# SDCardButtonLed.net
KiCad netlist of a schematic drawn in Altium Designer
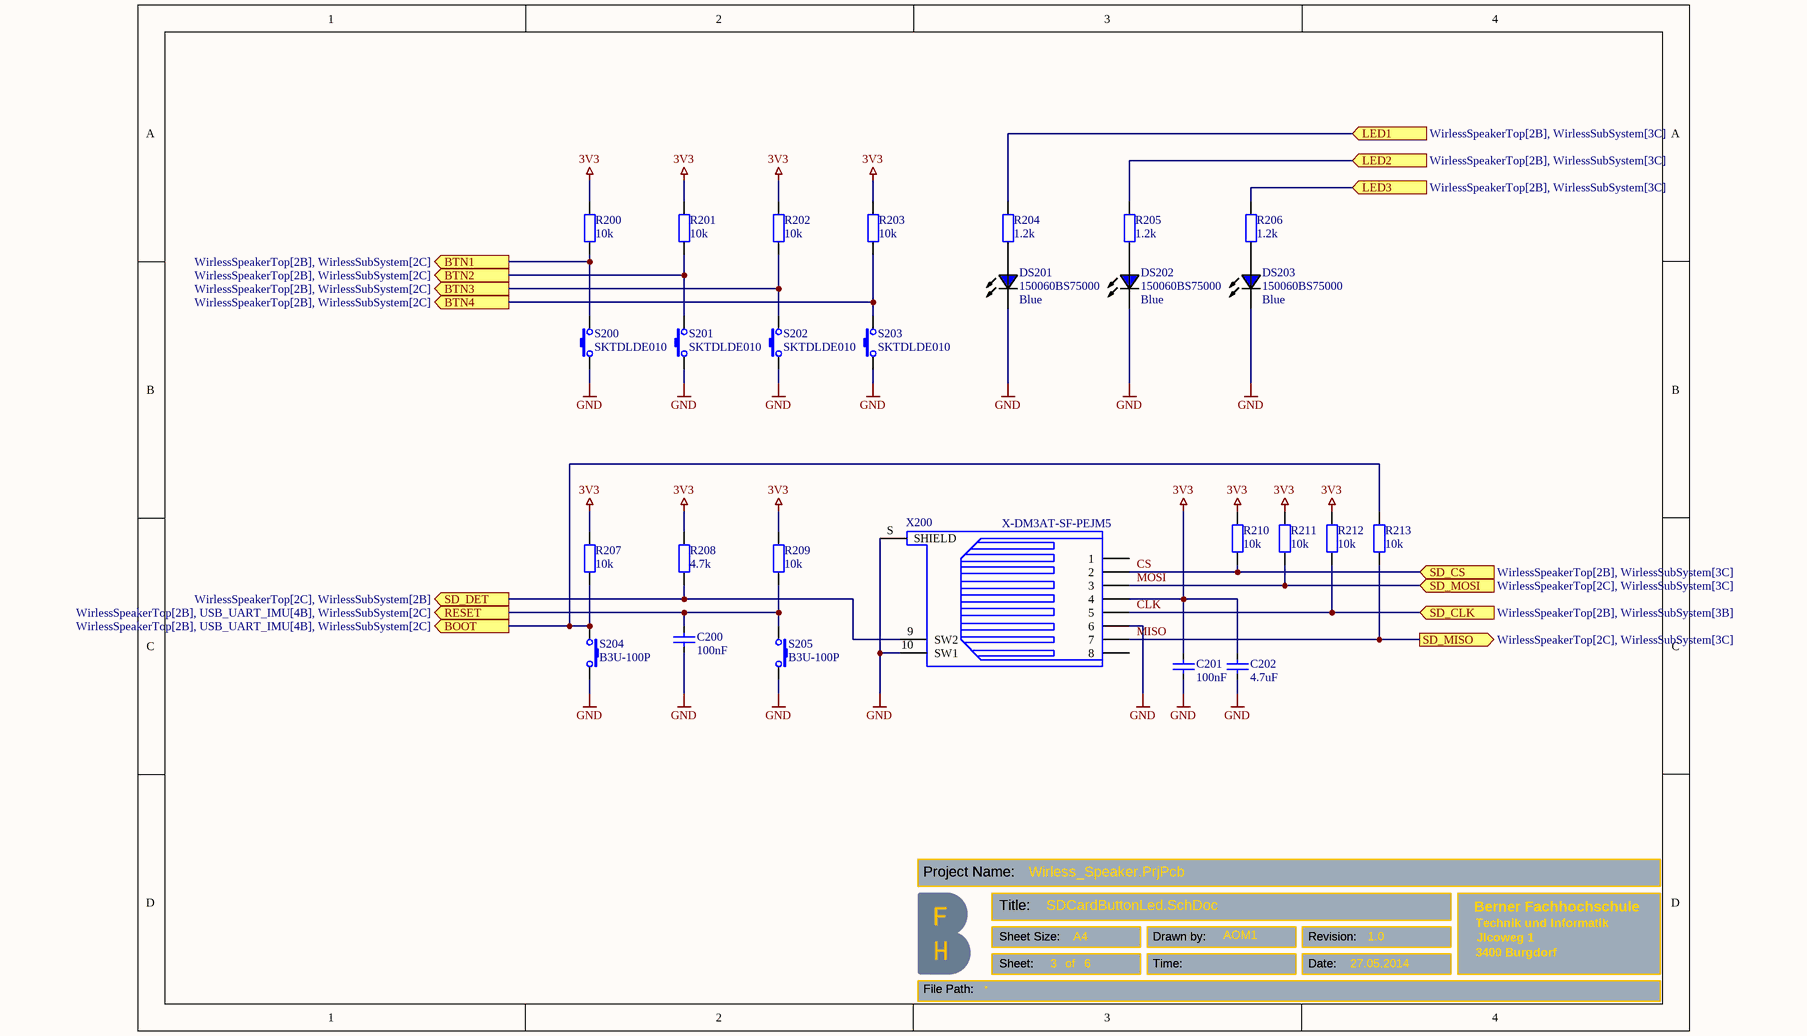
[diagram p0: SDCardButtonLed.SchDoc]

(export (version "E")
  (design (tool "Eeschema 10.0.6"))
  (components
    (comp (ref "C200")
      (value "100nF")
      (footprint "C-0603")
      (description "Multilayer Ceramic Capacitors MLCC")
      (fields (field (name "MANUFACTURER") "Murata Electronics") (field (name "MFR. PART NO.") "GRM18..."))
      (libsource (lib "WirelessAudioSpeaker") (part "C-SMD-0603"))
    )
    (comp (ref "C201")
      (value "100nF")
      (footprint "C-0603")
      (description "Multilayer Ceramic Capacitors MLCC")
      (fields (field (name "MANUFACTURER") "Murata Electronics") (field (name "MFR. PART NO.") "GRM18..."))
      (libsource (lib "WirelessAudioSpeaker") (part "C-SMD-0603"))
    )
    (comp (ref "C202")
      (value "4.7uF")
      (footprint "C-0603")
      (description "Multilayer Ceramic Capacitors MLCC")
      (fields (field (name "MANUFACTURER") "Murata Electronics") (field (name "MFR. PART NO.") "GRM18..."))
      (libsource (lib "WirelessAudioSpeaker") (part "C-SMD-0603"))
    )
    (comp (ref "DS201")
      (value "150060BS75000")
      (footprint "LED-0603-BLUE")
      (description "Standard LEDs - SMD 0603 Blue")
      (fields (field (name "MANUFACTURER") "Wurth Elektronik") (field (name "ALTIUM_VALUE") "Blue"))
      (libsource (lib "WirelessAudioSpeaker") (part "DS-LED-BLUE"))
    )
    (comp (ref "DS202")
      (value "150060BS75000")
      (footprint "LED-0603-BLUE")
      (description "Standard LEDs - SMD 0603 Blue")
      (fields (field (name "MANUFACTURER") "Wurth Elektronik") (field (name "ALTIUM_VALUE") "Blue"))
      (libsource (lib "WirelessAudioSpeaker") (part "DS-LED-BLUE"))
    )
    (comp (ref "DS203")
      (value "150060BS75000")
      (footprint "LED-0603-BLUE")
      (description "Standard LEDs - SMD 0603 Blue")
      (fields (field (name "MANUFACTURER") "Wurth Elektronik") (field (name "ALTIUM_VALUE") "Blue"))
      (libsource (lib "WirelessAudioSpeaker") (part "DS-LED-BLUE"))
    )
    (comp (ref "R200")
      (value "10k")
      (footprint "R-0603")
      (description "Thin Film Resistors - SMD  0.1W  1%")
      (fields (field (name "MFR. PART NO.") "MCU08050C*") (field (name "MANUFACTURER") "Vishay / Beyschlag"))
      (libsource (lib "WirelessAudioSpeaker") (part "R-SMD-0603"))
    )
    (comp (ref "R201")
      (value "10k")
      (footprint "R-0603")
      (description "Thin Film Resistors - SMD  0.1W  1%")
      (fields (field (name "MFR. PART NO.") "MCU08050C*") (field (name "MANUFACTURER") "Vishay / Beyschlag"))
      (libsource (lib "WirelessAudioSpeaker") (part "R-SMD-0603"))
    )
    (comp (ref "R202")
      (value "10k")
      (footprint "R-0603")
      (description "Thin Film Resistors - SMD  0.1W  1%")
      (fields (field (name "MFR. PART NO.") "MCU08050C*") (field (name "MANUFACTURER") "Vishay / Beyschlag"))
      (libsource (lib "WirelessAudioSpeaker") (part "R-SMD-0603"))
    )
    (comp (ref "R203")
      (value "10k")
      (footprint "R-0603")
      (description "Thin Film Resistors - SMD  0.1W  1%")
      (fields (field (name "MFR. PART NO.") "MCU08050C*") (field (name "MANUFACTURER") "Vishay / Beyschlag"))
      (libsource (lib "WirelessAudioSpeaker") (part "R-SMD-0603"))
    )
    (comp (ref "R204")
      (value "1.2k")
      (footprint "R-0603")
      (description "Thin Film Resistors - SMD  0.1W  1%")
      (fields (field (name "MFR. PART NO.") "MCU08050C*") (field (name "MANUFACTURER") "Vishay / Beyschlag"))
      (libsource (lib "WirelessAudioSpeaker") (part "R-SMD-0603"))
    )
    (comp (ref "R205")
      (value "1.2k")
      (footprint "R-0603")
      (description "Thin Film Resistors - SMD  0.1W  1%")
      (fields (field (name "MFR. PART NO.") "MCU08050C*") (field (name "MANUFACTURER") "Vishay / Beyschlag"))
      (libsource (lib "WirelessAudioSpeaker") (part "R-SMD-0603"))
    )
    (comp (ref "R206")
      (value "1.2k")
      (footprint "R-0603")
      (description "Thin Film Resistors - SMD  0.1W  1%")
      (fields (field (name "MFR. PART NO.") "MCU08050C*") (field (name "MANUFACTURER") "Vishay / Beyschlag"))
      (libsource (lib "WirelessAudioSpeaker") (part "R-SMD-0603"))
    )
    (comp (ref "R207")
      (value "10k")
      (footprint "R-0603")
      (description "Thin Film Resistors - SMD  0.1W  1%")
      (fields (field (name "MFR. PART NO.") "MCU08050C*") (field (name "MANUFACTURER") "Vishay / Beyschlag"))
      (libsource (lib "WirelessAudioSpeaker") (part "R-SMD-0603"))
    )
    (comp (ref "R208")
      (value "4.7k")
      (footprint "R-0603")
      (description "Thin Film Resistors - SMD  0.1W  1%")
      (fields (field (name "MFR. PART NO.") "MCU08050C*") (field (name "MANUFACTURER") "Vishay / Beyschlag"))
      (libsource (lib "WirelessAudioSpeaker") (part "R-SMD-0603"))
    )
    (comp (ref "R209")
      (value "10k")
      (footprint "R-0603")
      (description "Thin Film Resistors - SMD  0.1W  1%")
      (fields (field (name "MFR. PART NO.") "MCU08050C*") (field (name "MANUFACTURER") "Vishay / Beyschlag"))
      (libsource (lib "WirelessAudioSpeaker") (part "R-SMD-0603"))
    )
    (comp (ref "R210")
      (value "10k")
      (footprint "R-0603")
      (description "Thin Film Resistors - SMD  0.1W  1%")
      (fields (field (name "MFR. PART NO.") "MCU08050C*") (field (name "MANUFACTURER") "Vishay / Beyschlag"))
      (libsource (lib "WirelessAudioSpeaker") (part "R-SMD-0603"))
    )
    (comp (ref "R211")
      (value "10k")
      (footprint "R-0603")
      (description "Thin Film Resistors - SMD  0.1W  1%")
      (fields (field (name "MFR. PART NO.") "MCU08050C*") (field (name "MANUFACTURER") "Vishay / Beyschlag"))
      (libsource (lib "WirelessAudioSpeaker") (part "R-SMD-0603"))
    )
    (comp (ref "R212")
      (value "10k")
      (footprint "R-0603")
      (description "Thin Film Resistors - SMD  0.1W  1%")
      (fields (field (name "MFR. PART NO.") "MCU08050C*") (field (name "MANUFACTURER") "Vishay / Beyschlag"))
      (libsource (lib "WirelessAudioSpeaker") (part "R-SMD-0603"))
    )
    (comp (ref "R213")
      (value "10k")
      (footprint "R-0603")
      (description "Thin Film Resistors - SMD  0.1W  1%")
      (fields (field (name "MFR. PART NO.") "MCU08050C*") (field (name "MANUFACTURER") "Vishay / Beyschlag"))
      (libsource (lib "WirelessAudioSpeaker") (part "R-SMD-0603"))
    )
    (comp (ref "S200")
      (value "SKTDLDE010")
      (footprint "S-SKTDLDE010")
      (description "Tactile Switches 6x6 Flat 4.3mm Btn Force 100g w/o Grd")
      (fields (field (name "MANUFACTURER") "ALPS"))
      (libsource (lib "WirelessAudioSpeaker") (part "S-Tactile-Switch"))
    )
    (comp (ref "S201")
      (value "SKTDLDE010")
      (footprint "S-SKTDLDE010")
      (description "Tactile Switches 6x6 Flat 4.3mm Btn Force 100g w/o Grd")
      (fields (field (name "MANUFACTURER") "ALPS"))
      (libsource (lib "WirelessAudioSpeaker") (part "S-Tactile-Switch"))
    )
    (comp (ref "S202")
      (value "SKTDLDE010")
      (footprint "S-SKTDLDE010")
      (description "Tactile Switches 6x6 Flat 4.3mm Btn Force 100g w/o Grd")
      (fields (field (name "MANUFACTURER") "ALPS"))
      (libsource (lib "WirelessAudioSpeaker") (part "S-Tactile-Switch"))
    )
    (comp (ref "S203")
      (value "SKTDLDE010")
      (footprint "S-SKTDLDE010")
      (description "Tactile Switches 6x6 Flat 4.3mm Btn Force 100g w/o Grd")
      (fields (field (name "MANUFACTURER") "ALPS"))
      (libsource (lib "WirelessAudioSpeaker") (part "S-Tactile-Switch"))
    )
    (comp (ref "S204")
      (value "B3U-100P")
      (footprint "S-B3U-100X")
      (description "Tactile Switches Top Actuated w/o boss w/o ground")
      (fields
        (field (name "MANUFACTURER") "OMRON ELECTRONIC COMPONENTS")
        (field (name "MFR. PART NO.") "B3U-1000P")
      )
      (libsource (lib "WirelessAudioSpeaker") (part "S-B3U-100P"))
    )
    (comp (ref "S205")
      (value "B3U-100P")
      (footprint "S-B3U-100X")
      (description "Tactile Switches Top Actuated w/o boss w/o ground")
      (fields
        (field (name "MANUFACTURER") "OMRON ELECTRONIC COMPONENTS")
        (field (name "MFR. PART NO.") "B3U-1000P")
      )
      (libsource (lib "WirelessAudioSpeaker") (part "S-B3U-100P"))
    )
    (comp (ref "X200")
      (value "X-DM3AT-SF-PEJM5")
      (footprint "X-DM3AT-SF-PEJM5")
      (description "SMTMicro SD 8 Pin PCB")
      (fields
        (field (name "MANUFACTURER") "Hirose Electric Co Ltd")
        (field (name "MFR. PART NO.") "DM3AT-SF-PEJM5")
      )
      (libsource (lib "WirelessAudioSpeaker") (part "X-DM3AT-SF-PEJM5"))
    )
  )
  (nets
    (net (code "1") (name "/BOOT") (class "Default")
      (node (ref "R207") (pin "1") (pinfunction "1_1") (pintype "passive"))
      (node (ref "R213") (pin "2") (pinfunction "2_2") (pintype "passive"))
      (node (ref "S204") (pin "1") (pinfunction "1_1") (pintype "passive"))
    )
    (net (code "2") (name "/BTN1") (class "Default")
      (node (ref "R200") (pin "1") (pinfunction "1_1") (pintype "passive"))
      (node (ref "S200") (pin "2") (pinfunction "2_2") (pintype "passive"))
    )
    (net (code "3") (name "/BTN2") (class "Default")
      (node (ref "R201") (pin "1") (pinfunction "1_1") (pintype "passive"))
      (node (ref "S201") (pin "2") (pinfunction "2_2") (pintype "passive"))
    )
    (net (code "4") (name "/BTN3") (class "Default")
      (node (ref "R202") (pin "1") (pinfunction "1_1") (pintype "passive"))
      (node (ref "S202") (pin "2") (pinfunction "2_2") (pintype "passive"))
    )
    (net (code "5") (name "/BTN4") (class "Default")
      (node (ref "R203") (pin "1") (pinfunction "1_1") (pintype "passive"))
      (node (ref "S203") (pin "2") (pinfunction "2_2") (pintype "passive"))
    )
    (net (code "6") (name "/CLK") (class "Default")
      (node (ref "R212") (pin "1") (pinfunction "1_1") (pintype "passive"))
      (node (ref "X200") (pin "5") (pinfunction "5_5") (pintype "passive"))
    )
    (net (code "7") (name "/CS") (class "Default")
      (node (ref "R210") (pin "1") (pinfunction "1_1") (pintype "passive"))
      (node (ref "X200") (pin "2") (pinfunction "2_2") (pintype "passive"))
    )
    (net (code "8") (name "/LED1") (class "Default")
      (node (ref "R204") (pin "2") (pinfunction "2_2") (pintype "passive"))
    )
    (net (code "9") (name "/LED2") (class "Default")
      (node (ref "R205") (pin "2") (pinfunction "2_2") (pintype "passive"))
    )
    (net (code "10") (name "/LED3") (class "Default")
      (node (ref "R206") (pin "2") (pinfunction "2_2") (pintype "passive"))
    )
    (net (code "11") (name "/MISO") (class "Default")
      (node (ref "R213") (pin "1") (pinfunction "1_1") (pintype "passive"))
      (node (ref "X200") (pin "7") (pinfunction "7_7") (pintype "passive"))
    )
    (net (code "12") (name "/MOSI") (class "Default")
      (node (ref "R211") (pin "1") (pinfunction "1_1") (pintype "passive"))
      (node (ref "X200") (pin "3") (pinfunction "3_3") (pintype "passive"))
    )
    (net (code "13") (name "/RESET") (class "Default")
      (node (ref "C200") (pin "2") (pinfunction "2_2") (pintype "passive"))
      (node (ref "R209") (pin "1") (pinfunction "1_1") (pintype "passive"))
      (node (ref "S205") (pin "1") (pinfunction "1_1") (pintype "passive"))
    )
    (net (code "14") (name "/SD_DET") (class "Default")
      (node (ref "R208") (pin "1") (pinfunction "1_1") (pintype "passive"))
      (node (ref "X200") (pin "9") (pinfunction "SW2_9") (pintype "passive"))
    )
    (net (code "15") (name "3V3") (class "Default")
      (node (ref "C201") (pin "2") (pinfunction "2_2") (pintype "passive"))
      (node (ref "C202") (pin "2") (pinfunction "2_2") (pintype "passive"))
      (node (ref "R200") (pin "2") (pinfunction "2_2") (pintype "passive"))
      (node (ref "R201") (pin "2") (pinfunction "2_2") (pintype "passive"))
      (node (ref "R202") (pin "2") (pinfunction "2_2") (pintype "passive"))
      (node (ref "R203") (pin "2") (pinfunction "2_2") (pintype "passive"))
      (node (ref "R207") (pin "2") (pinfunction "2_2") (pintype "passive"))
      (node (ref "R208") (pin "2") (pinfunction "2_2") (pintype "passive"))
      (node (ref "R209") (pin "2") (pinfunction "2_2") (pintype "passive"))
      (node (ref "R210") (pin "2") (pinfunction "2_2") (pintype "passive"))
      (node (ref "R211") (pin "2") (pinfunction "2_2") (pintype "passive"))
      (node (ref "R212") (pin "2") (pinfunction "2_2") (pintype "passive"))
      (node (ref "X200") (pin "4") (pinfunction "4_4") (pintype "passive"))
    )
    (net (code "16") (name "GND") (class "Default")
      (node (ref "C200") (pin "1") (pinfunction "1_1") (pintype "passive"))
      (node (ref "C201") (pin "1") (pinfunction "1_1") (pintype "passive"))
      (node (ref "C202") (pin "1") (pinfunction "1_1") (pintype "passive"))
      (node (ref "DS201") (pin "K") (pinfunction "K_K") (pintype "passive"))
      (node (ref "DS202") (pin "K") (pinfunction "K_K") (pintype "passive"))
      (node (ref "DS203") (pin "K") (pinfunction "K_K") (pintype "passive"))
      (node (ref "S200") (pin "1") (pinfunction "1_1") (pintype "passive"))
      (node (ref "S201") (pin "1") (pinfunction "1_1") (pintype "passive"))
      (node (ref "S202") (pin "1") (pinfunction "1_1") (pintype "passive"))
      (node (ref "S203") (pin "1") (pinfunction "1_1") (pintype "passive"))
      (node (ref "S204") (pin "2") (pinfunction "2_2") (pintype "passive"))
      (node (ref "S205") (pin "2") (pinfunction "2_2") (pintype "passive"))
      (node (ref "X200") (pin "10") (pinfunction "SW1_10") (pintype "passive"))
      (node (ref "X200") (pin "6") (pinfunction "6_6") (pintype "passive"))
      (node (ref "X200") (pin "S") (pinfunction "SHIELD_S") (pintype "passive"))
    )
    (net (code "17") (name "Net-(DS201-PadA)") (class "Default")
      (node (ref "DS201") (pin "A") (pinfunction "A_A") (pintype "passive"))
      (node (ref "R204") (pin "1") (pinfunction "1_1") (pintype "passive"))
    )
    (net (code "18") (name "Net-(DS202-PadA)") (class "Default")
      (node (ref "DS202") (pin "A") (pinfunction "A_A") (pintype "passive"))
      (node (ref "R205") (pin "1") (pinfunction "1_1") (pintype "passive"))
    )
    (net (code "19") (name "Net-(DS203-PadA)") (class "Default")
      (node (ref "DS203") (pin "A") (pinfunction "A_A") (pintype "passive"))
      (node (ref "R206") (pin "1") (pinfunction "1_1") (pintype "passive"))
    )
    (net (code "20") (name "unconnected-(X200-Pad1)") (class "Default")
      (node (ref "X200") (pin "1") (pinfunction "1_1") (pintype "passive"))
    )
    (net (code "21") (name "unconnected-(X200-Pad8)") (class "Default")
      (node (ref "X200") (pin "8") (pinfunction "8_8") (pintype "passive"))
    )
  )
)
